# TURBINE.net
KiCad netlist of a schematic drawn in Altium Designer
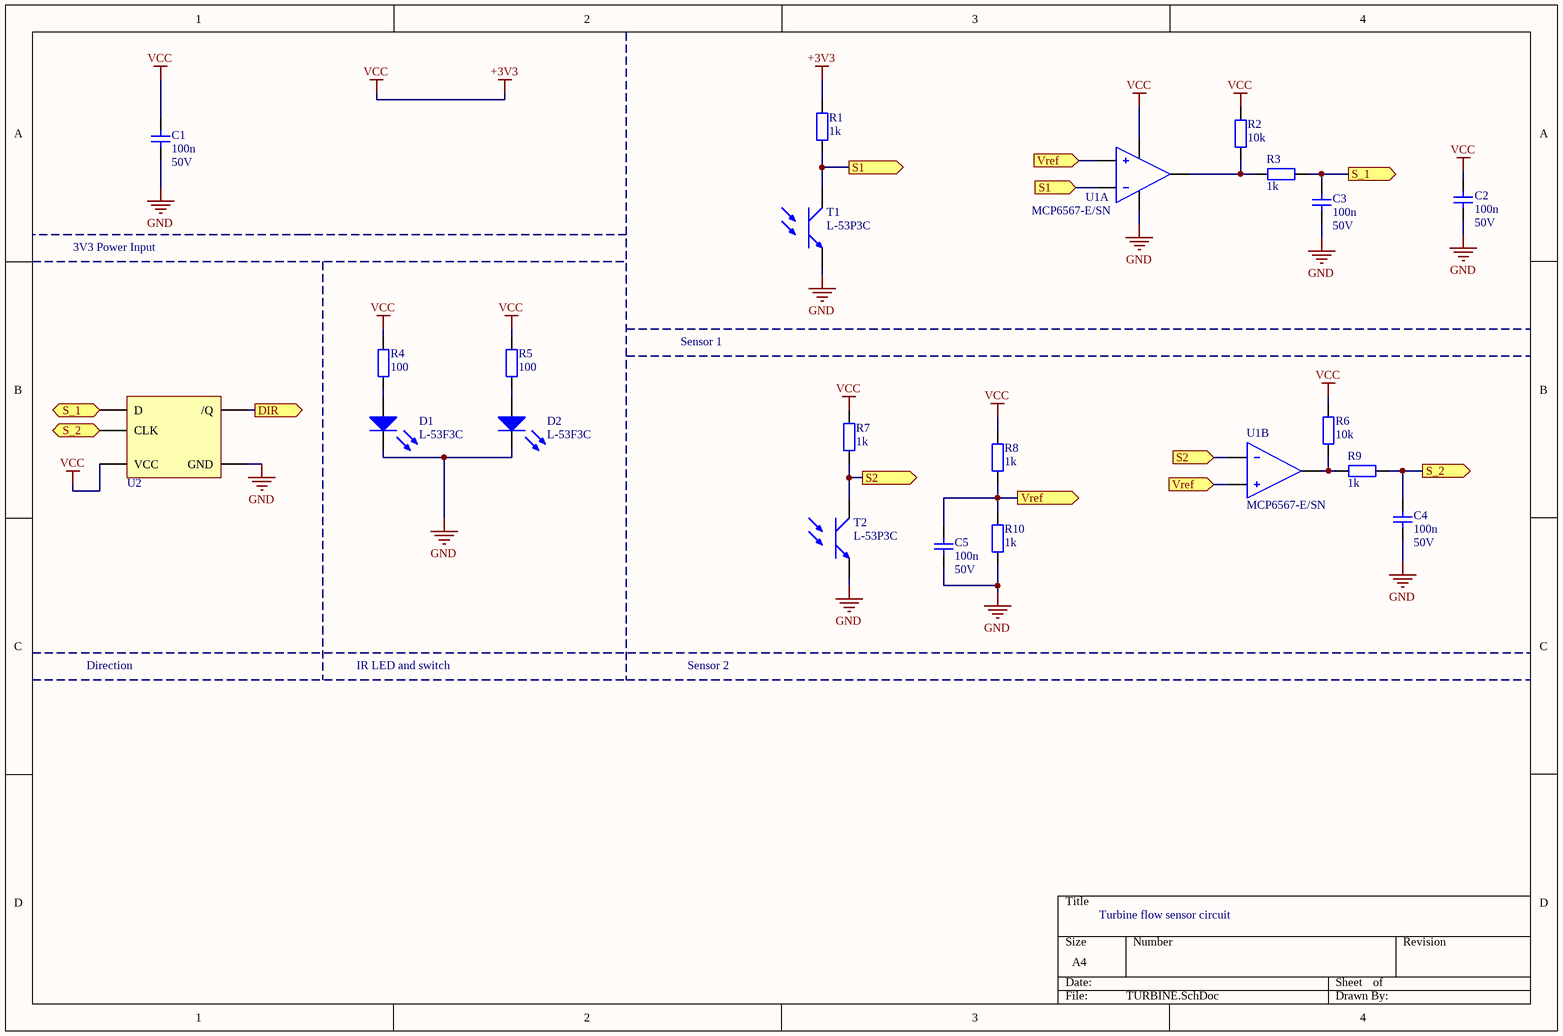
[diagram p0: TURBINE.SchDoc]

(export (version "E")
  (design (tool "Eeschema 10.0.6"))
  (components
    (comp (ref "C1")
      (value "100n")
      (footprint "C1206")
      (description "Capacitor")
      (fields (field (name "VOLTAGE RATING") "50V") (field (name "Comment") "CAP"))
      (libsource (lib "Turbine_Lib") (part "CAP"))
    )
    (comp (ref "C2")
      (value "100n")
      (footprint "C1206")
      (description "Capacitor")
      (fields (field (name "VOLTAGE RATING") "50V") (field (name "Comment") "CAP"))
      (libsource (lib "Turbine_Lib") (part "CAP"))
    )
    (comp (ref "C3")
      (value "100n")
      (footprint "C1206")
      (description "Capacitor")
      (fields (field (name "VOLTAGE RATING") "50V") (field (name "Comment") "CAP"))
      (libsource (lib "Turbine_Lib") (part "CAP"))
    )
    (comp (ref "C4")
      (value "100n")
      (footprint "C1206")
      (description "Capacitor")
      (fields (field (name "VOLTAGE RATING") "50V") (field (name "Comment") "CAP"))
      (libsource (lib "Turbine_Lib") (part "CAP"))
    )
    (comp (ref "C5")
      (value "100n")
      (footprint "C1206")
      (description "Capacitor")
      (fields (field (name "VOLTAGE RATING") "50V") (field (name "Comment") "CAP"))
      (libsource (lib "Turbine_Lib") (part "CAP"))
    )
    (comp (ref "D1")
      (value "L-53F3C")
      (footprint "5mm LED")
      (description "L-53F3C- IR EMITTING DIODE, 940NM, 5MM")
      (fields (field (name "MANUFACTURER") "KINGBRIGHT"))
      (libsource (lib "Turbine_Lib") (part "L-53F3C"))
    )
    (comp (ref "D2")
      (value "L-53F3C")
      (footprint "5mm LED")
      (description "L-53F3C- IR EMITTING DIODE, 940NM, 5MM")
      (fields (field (name "MANUFACTURER") "KINGBRIGHT"))
      (libsource (lib "Turbine_Lib") (part "L-53F3C"))
    )
    (comp (ref "R1")
      (value "1k")
      (footprint "R1206")
      (description "1206 Resistor")
      (fields (field (name "Comment") "1206"))
      (libsource (lib "Turbine_Lib") (part "RES"))
    )
    (comp (ref "R2")
      (value "10k")
      (footprint "R1206")
      (description "1206 Resistor")
      (fields (field (name "Comment") "1206"))
      (libsource (lib "Turbine_Lib") (part "RES"))
    )
    (comp (ref "R3")
      (value "1k")
      (footprint "R1206")
      (description "1206 Resistor")
      (fields (field (name "Comment") "1206"))
      (libsource (lib "Turbine_Lib") (part "RES"))
    )
    (comp (ref "R4")
      (value "100")
      (footprint "R1206")
      (description "1206 Resistor")
      (fields (field (name "Comment") "1206"))
      (libsource (lib "Turbine_Lib") (part "RES"))
    )
    (comp (ref "R5")
      (value "100")
      (footprint "R1206")
      (description "1206 Resistor")
      (fields (field (name "Comment") "1206"))
      (libsource (lib "Turbine_Lib") (part "RES"))
    )
    (comp (ref "R6")
      (value "10k")
      (footprint "R1206")
      (description "1206 Resistor")
      (fields (field (name "Comment") "1206"))
      (libsource (lib "Turbine_Lib") (part "RES"))
    )
    (comp (ref "R7")
      (value "1k")
      (footprint "R1206")
      (description "1206 Resistor")
      (fields (field (name "Comment") "1206"))
      (libsource (lib "Turbine_Lib") (part "RES"))
    )
    (comp (ref "R8")
      (value "1k")
      (footprint "R1206")
      (description "1206 Resistor")
      (fields (field (name "Comment") "1206"))
      (libsource (lib "Turbine_Lib") (part "RES"))
    )
    (comp (ref "R9")
      (value "1k")
      (footprint "R1206")
      (description "1206 Resistor")
      (fields (field (name "Comment") "1206"))
      (libsource (lib "Turbine_Lib") (part "RES"))
    )
    (comp (ref "R10")
      (value "1k")
      (footprint "R1206")
      (description "1206 Resistor")
      (fields (field (name "Comment") "1206"))
      (libsource (lib "Turbine_Lib") (part "RES"))
    )
    (comp (ref "T1")
      (value "L-53P3C")
      (footprint "5mm LED")
      (description "L-53P3C- PHOTO TRANSISTOR, NPN 5mm")
      (fields (field (name "MANUFACTURER") "KINGBRIGHT"))
      (libsource (lib "Turbine_Lib") (part "L-53P3C"))
    )
    (comp (ref "T2")
      (value "L-53P3C")
      (footprint "5mm LED")
      (description "L-53P3C- PHOTO TRANSISTOR, NPN 5mm")
      (fields (field (name "MANUFACTURER") "KINGBRIGHT"))
      (libsource (lib "Turbine_Lib") (part "L-53P3C"))
    )
    (comp (ref "U1")
      (value "MCP6567-E/SN")
      (footprint "SOIC8")
      (description "MICROCHIP - MCP6567-E/SN - IC, COMPARATOR, DUAL, 1.8V, 8SOIC")
      (fields (field (name "MANUFACTURER") "MICROCHIP") (field (name "APPROVAL CATEGORY") "AEC-Q100"))
      (libsource (lib "Turbine_Lib") (part "MCP6567-E/SN"))
    )
    (comp (ref "U2")
      (value "SN74AUP1G80DCKR")
      (footprint "SOT23-5")
      (description "TEXAS INSTRUMENTS - SN74AUP1G80DCKR - FLIP FLOP, D-TYPE, 280MHZ, SC-70-5")
      (fields (field (name "MANUFACTURER") "TEXAS INSTRUMENTS"))
      (libsource (lib "Turbine_Lib") (part "SN74AUP1G80DCKR"))
    )
  )
  (nets
    (net (code "1") (name "+3V3") (class "Default")
      (node (ref "C1") (pin "1") (pinfunction "1_1") (pintype "passive"))
      (node (ref "C2") (pin "1") (pinfunction "1_1") (pintype "passive"))
      (node (ref "R1") (pin "1") (pinfunction "1_1") (pintype "passive"))
      (node (ref "R2") (pin "1") (pinfunction "1_1") (pintype "passive"))
      (node (ref "R4") (pin "1") (pinfunction "1_1") (pintype "passive"))
      (node (ref "R5") (pin "1") (pinfunction "1_1") (pintype "passive"))
      (node (ref "R6") (pin "1") (pinfunction "1_1") (pintype "passive"))
      (node (ref "R7") (pin "1") (pinfunction "1_1") (pintype "passive"))
      (node (ref "R8") (pin "1") (pinfunction "1_1") (pintype "passive"))
      (node (ref "U1") (pin "8") (pinfunction "VCC_8") (pintype "passive"))
      (node (ref "U2") (pin "5") (pinfunction "VCC_5") (pintype "passive"))
    )
    (net (code "2") (name "/DIR") (class "Default")
      (node (ref "U2") (pin "4") (pinfunction "/Q_4") (pintype "passive"))
    )
    (net (code "3") (name "/S1") (class "Default")
      (node (ref "R1") (pin "2") (pinfunction "2_2") (pintype "passive"))
      (node (ref "T1") (pin "1") (pinfunction "C_1") (pintype "passive"))
      (node (ref "U1") (pin "2") (pinfunction "INA-_2") (pintype "passive"))
    )
    (net (code "4") (name "/S2") (class "Default")
      (node (ref "R7") (pin "2") (pinfunction "2_2") (pintype "passive"))
      (node (ref "T2") (pin "1") (pinfunction "C_1") (pintype "passive"))
      (node (ref "U1") (pin "6") (pinfunction "INB-_6") (pintype "passive"))
    )
    (net (code "5") (name "/S_1") (class "Default")
      (node (ref "C3") (pin "1") (pinfunction "1_1") (pintype "passive"))
      (node (ref "R3") (pin "2") (pinfunction "2_2") (pintype "passive"))
      (node (ref "U2") (pin "1") (pinfunction "D_1") (pintype "passive"))
    )
    (net (code "6") (name "/S_2") (class "Default")
      (node (ref "C4") (pin "1") (pinfunction "1_1") (pintype "passive"))
      (node (ref "R9") (pin "2") (pinfunction "2_2") (pintype "passive"))
      (node (ref "U2") (pin "2") (pinfunction "CLK_2") (pintype "passive"))
    )
    (net (code "7") (name "/Vref") (class "Default")
      (node (ref "C5") (pin "2") (pinfunction "2_2") (pintype "passive"))
      (node (ref "R10") (pin "1") (pinfunction "1_1") (pintype "passive"))
      (node (ref "R8") (pin "2") (pinfunction "2_2") (pintype "passive"))
      (node (ref "U1") (pin "3") (pinfunction "INA+_3") (pintype "passive"))
      (node (ref "U1") (pin "5") (pinfunction "INB+_5") (pintype "passive"))
    )
    (net (code "8") (name "GND") (class "Default")
      (node (ref "C1") (pin "2") (pinfunction "2_2") (pintype "passive"))
      (node (ref "C2") (pin "2") (pinfunction "2_2") (pintype "passive"))
      (node (ref "C3") (pin "2") (pinfunction "2_2") (pintype "passive"))
      (node (ref "C4") (pin "2") (pinfunction "2_2") (pintype "passive"))
      (node (ref "C5") (pin "1") (pinfunction "1_1") (pintype "passive"))
      (node (ref "D1") (pin "1") (pinfunction "1_1") (pintype "passive"))
      (node (ref "D2") (pin "1") (pinfunction "1_1") (pintype "passive"))
      (node (ref "R10") (pin "2") (pinfunction "2_2") (pintype "passive"))
      (node (ref "T1") (pin "2") (pinfunction "E_2") (pintype "passive"))
      (node (ref "T2") (pin "2") (pinfunction "E_2") (pintype "passive"))
      (node (ref "U1") (pin "4") (pinfunction "VSS_4") (pintype "passive"))
      (node (ref "U2") (pin "3") (pinfunction "GND_3") (pintype "passive"))
    )
    (net (code "9") (name "Net-(D1-Pad2)") (class "Default")
      (node (ref "D1") (pin "2") (pinfunction "2_2") (pintype "passive"))
      (node (ref "R4") (pin "2") (pinfunction "2_2") (pintype "passive"))
    )
    (net (code "10") (name "Net-(D2-Pad2)") (class "Default")
      (node (ref "D2") (pin "2") (pinfunction "2_2") (pintype "passive"))
      (node (ref "R5") (pin "2") (pinfunction "2_2") (pintype "passive"))
    )
    (net (code "11") (name "Net-(U1A-VoutA)") (class "Default")
      (node (ref "R2") (pin "2") (pinfunction "2_2") (pintype "passive"))
      (node (ref "R3") (pin "1") (pinfunction "1_1") (pintype "passive"))
      (node (ref "U1") (pin "1") (pinfunction "VoutA_1") (pintype "passive"))
    )
    (net (code "12") (name "Net-(U1B-VoutB)") (class "Default")
      (node (ref "R6") (pin "2") (pinfunction "2_2") (pintype "passive"))
      (node (ref "R9") (pin "1") (pinfunction "1_1") (pintype "passive"))
      (node (ref "U1") (pin "7") (pinfunction "VoutB_7") (pintype "passive"))
    )
  )
)
